# UltiMem_v1_01.net
KiCad netlist of a schematic drawn in EAGLE
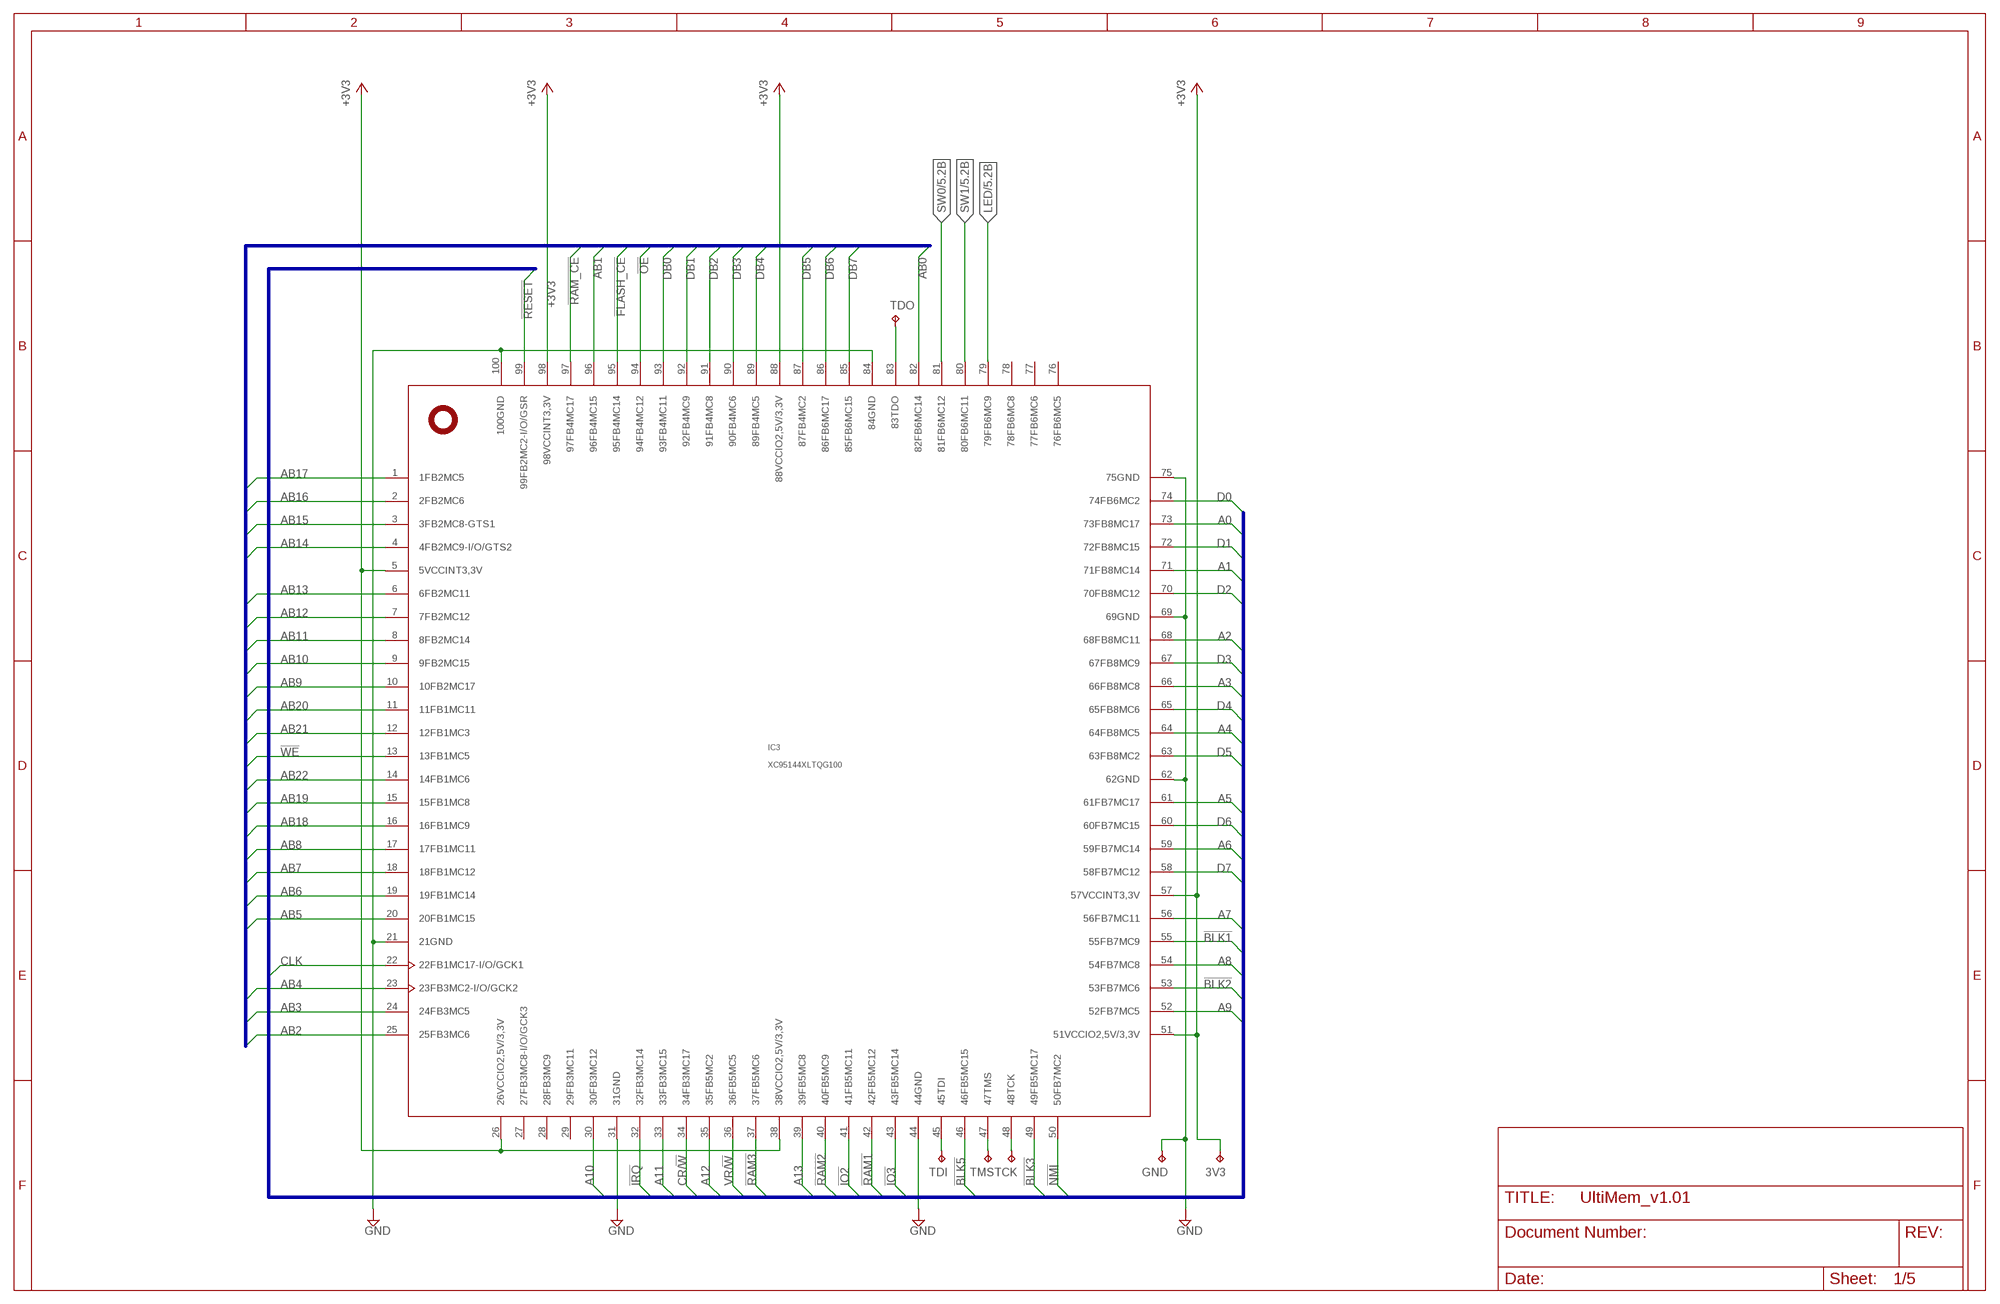
[diagram p0: schematic, sheet 1]
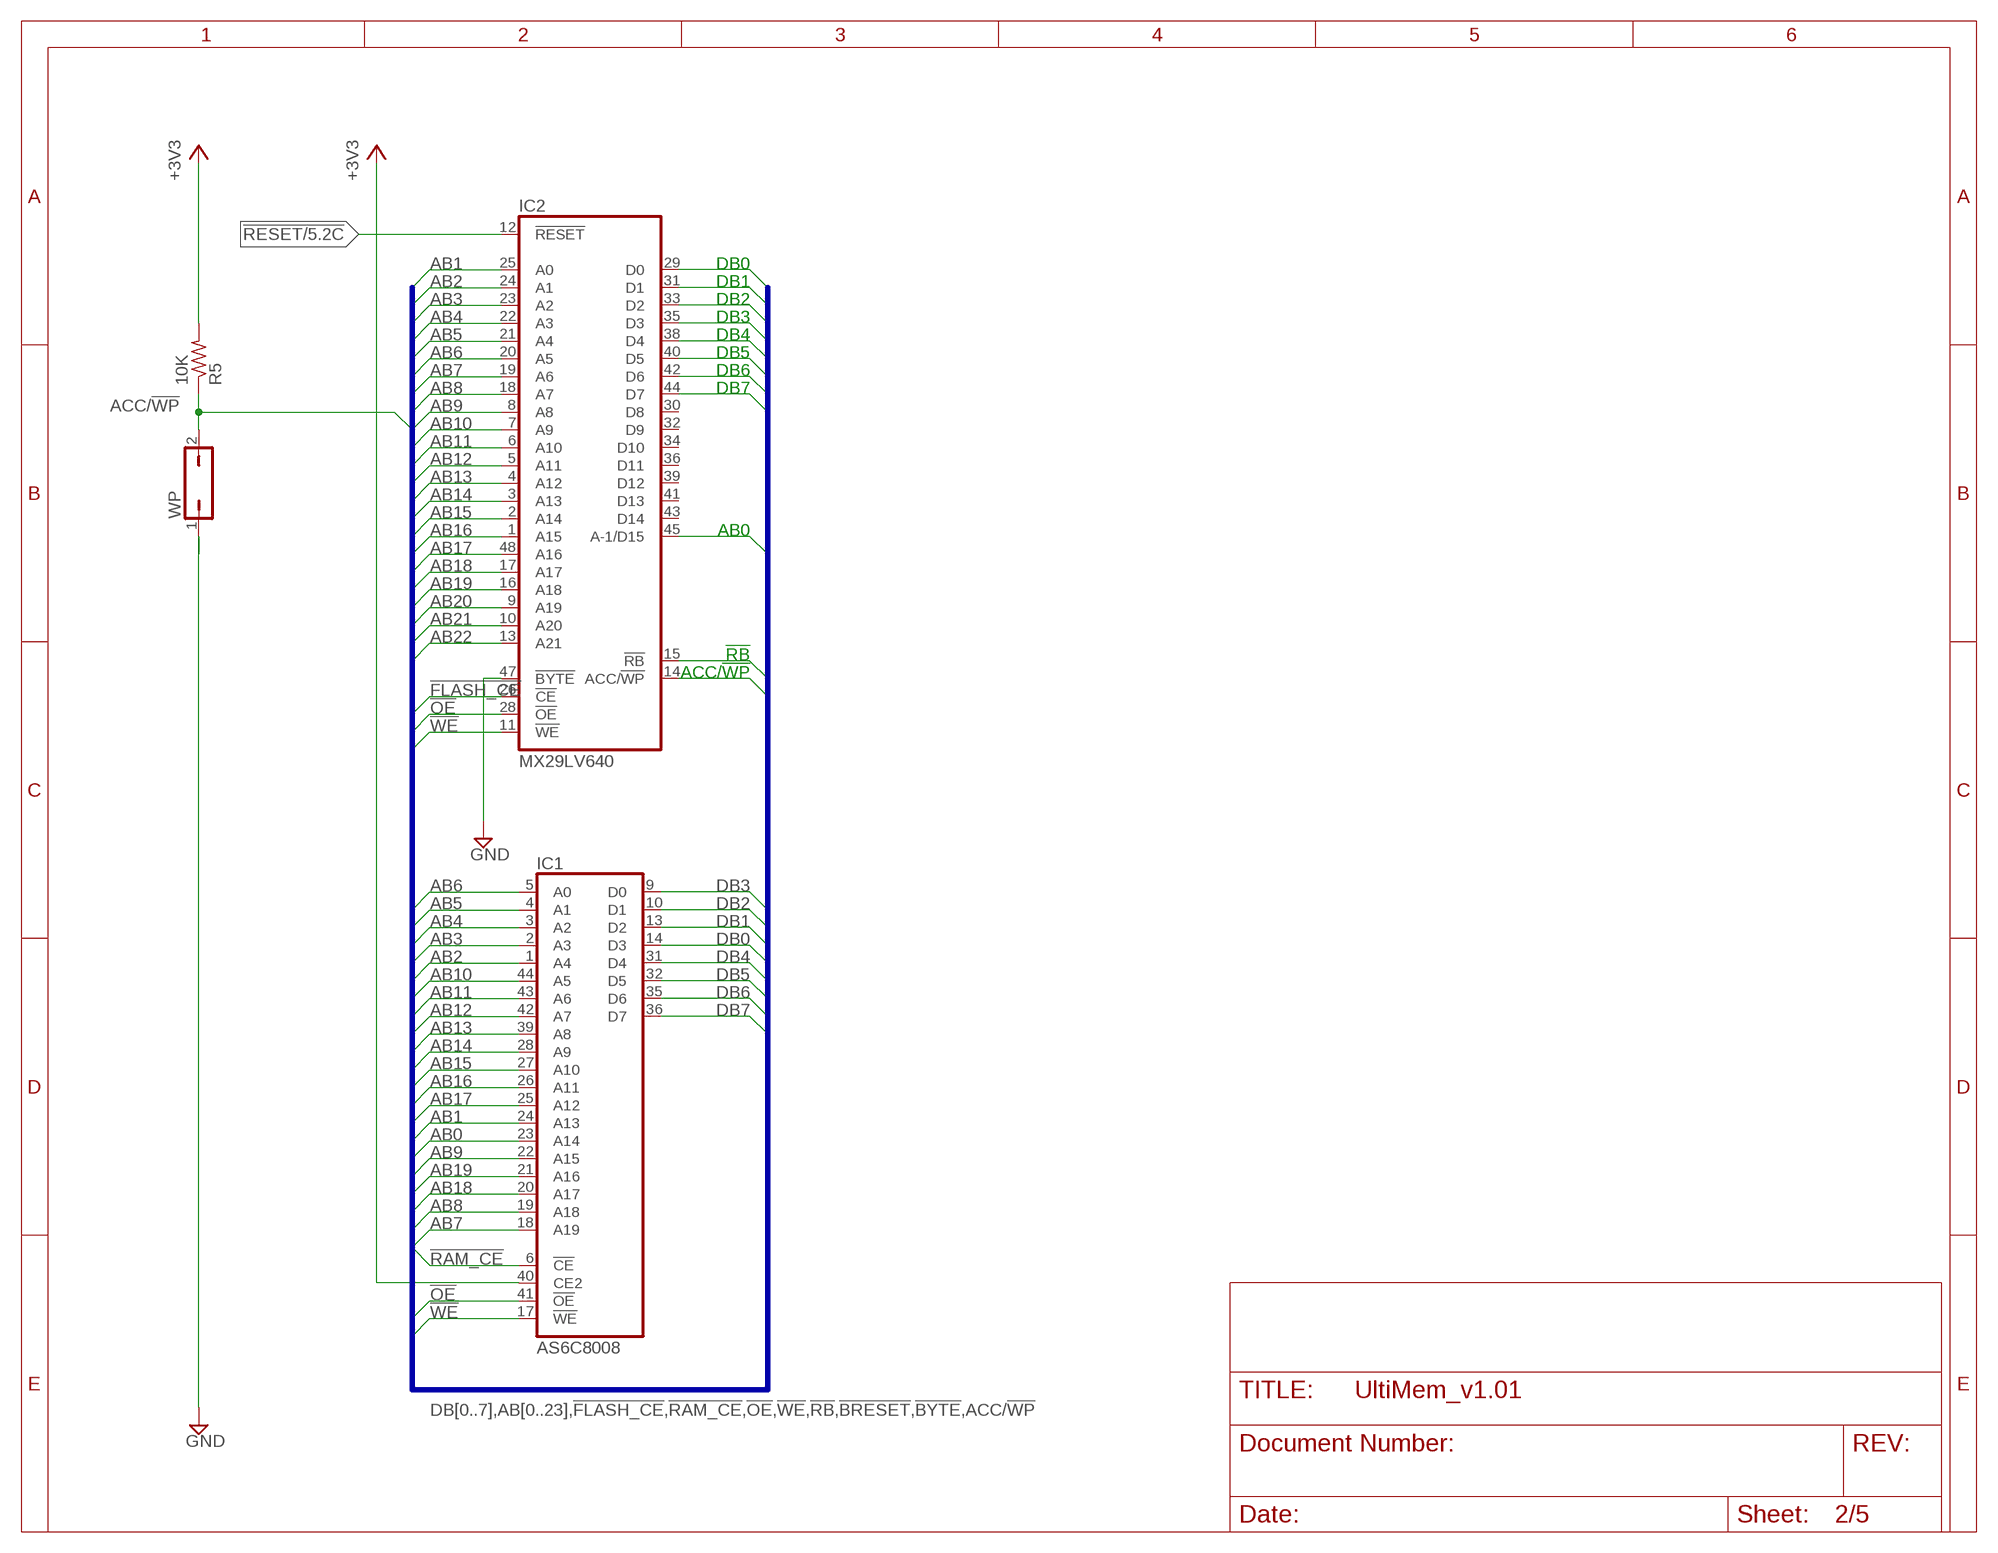
[diagram p1: schematic, sheet 2]
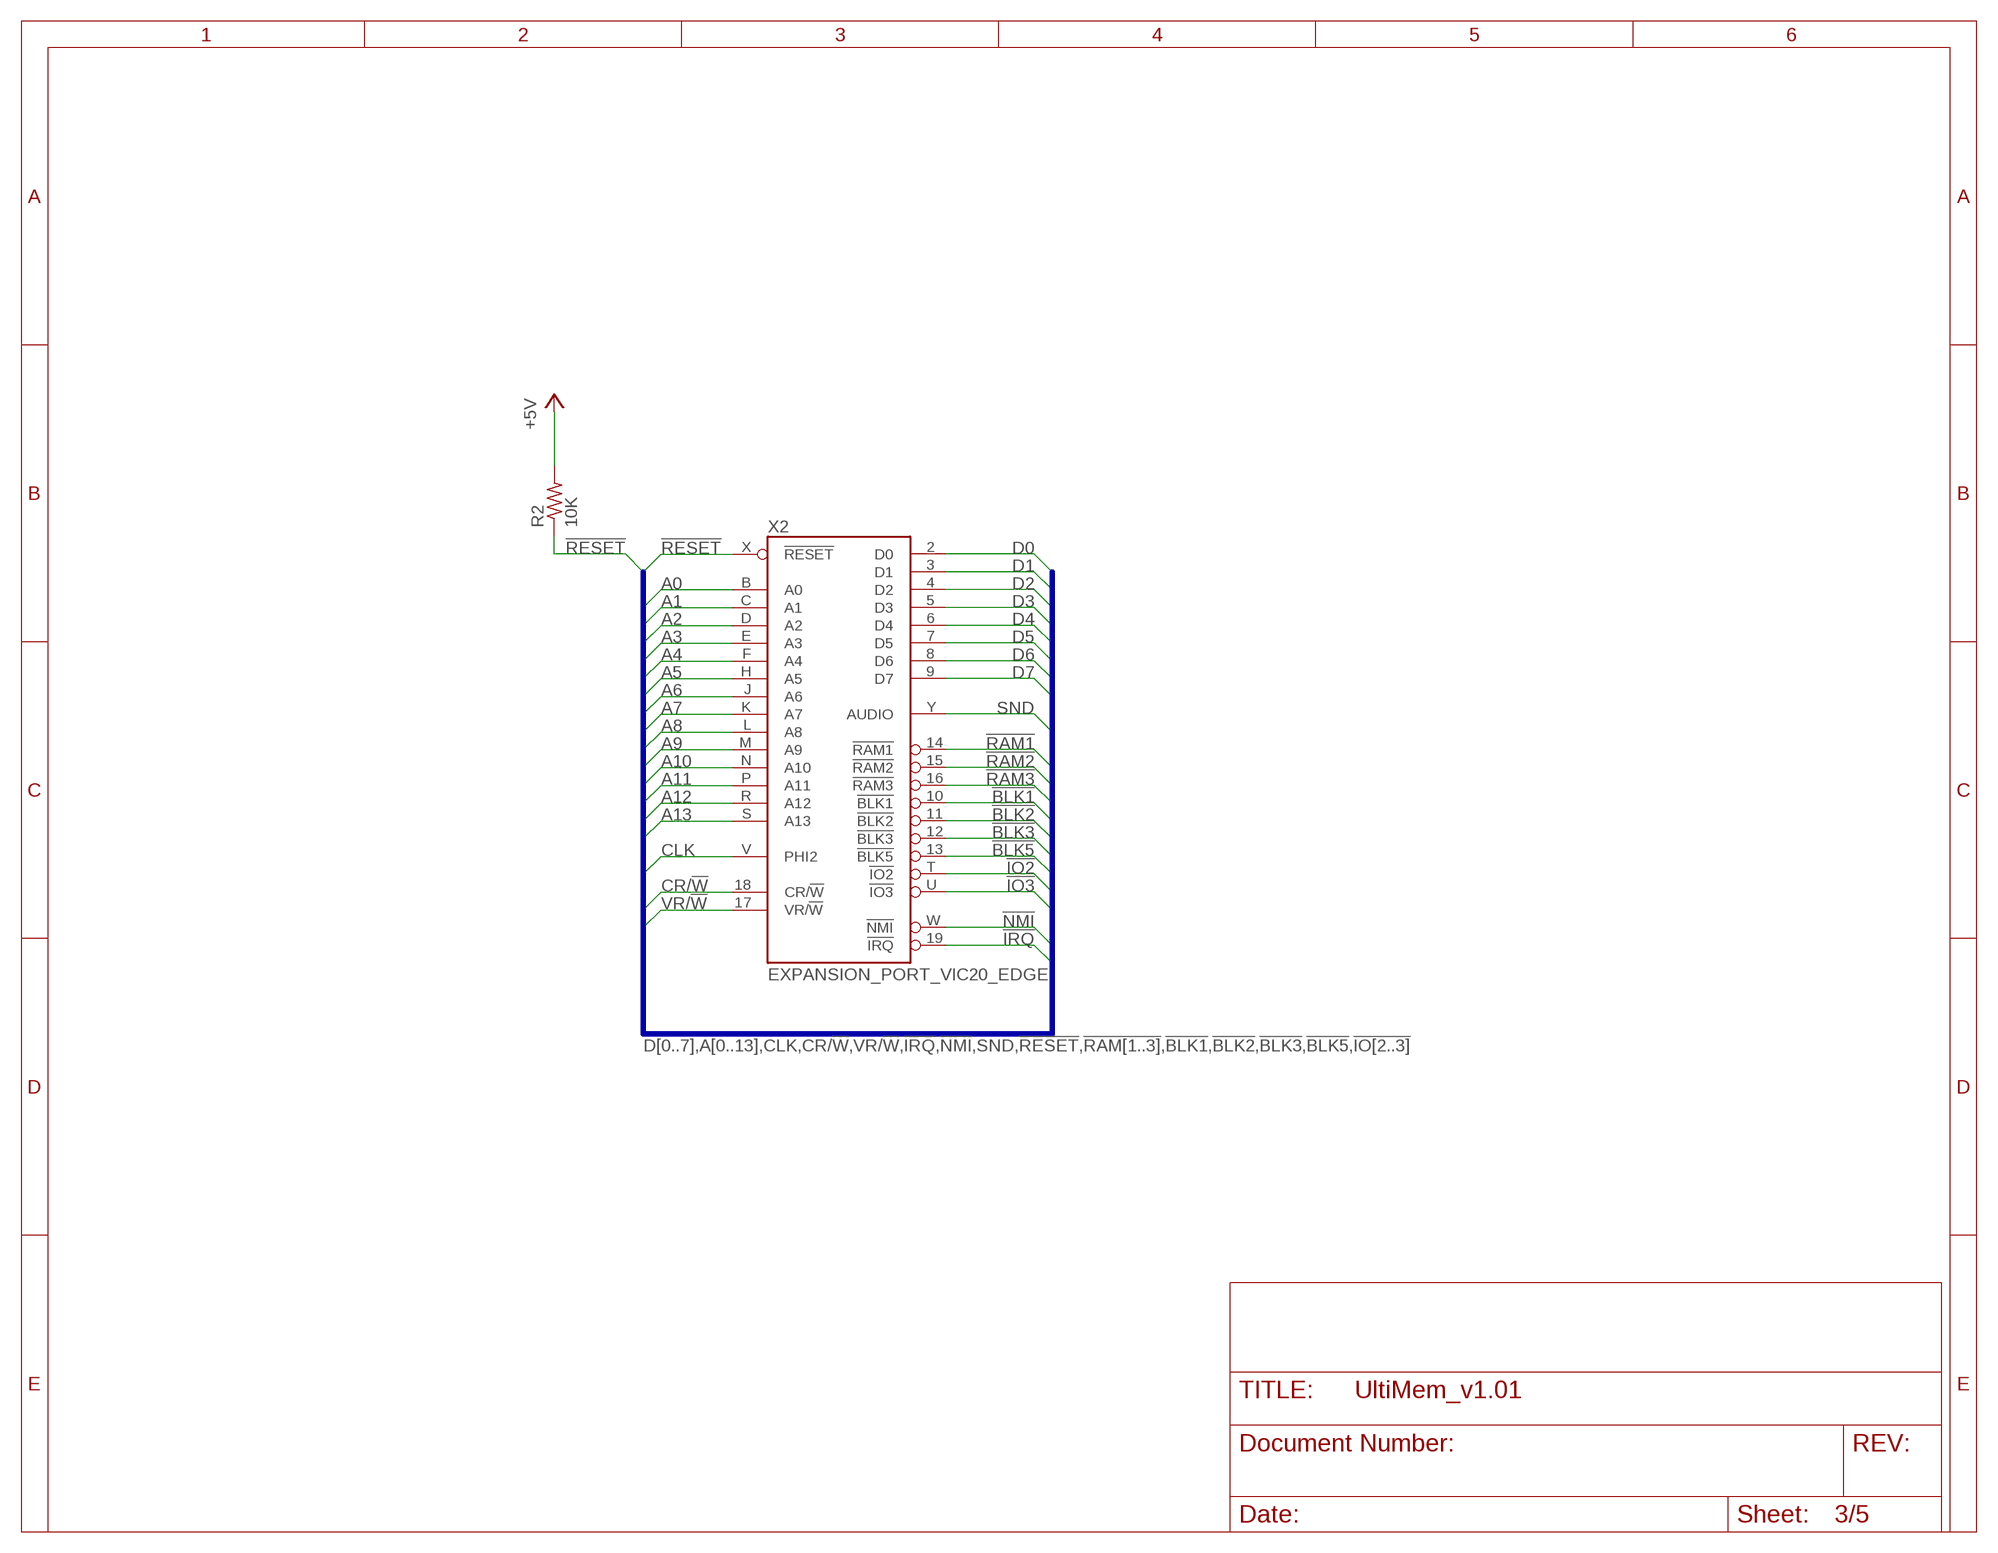
[diagram p2: schematic, sheet 3]
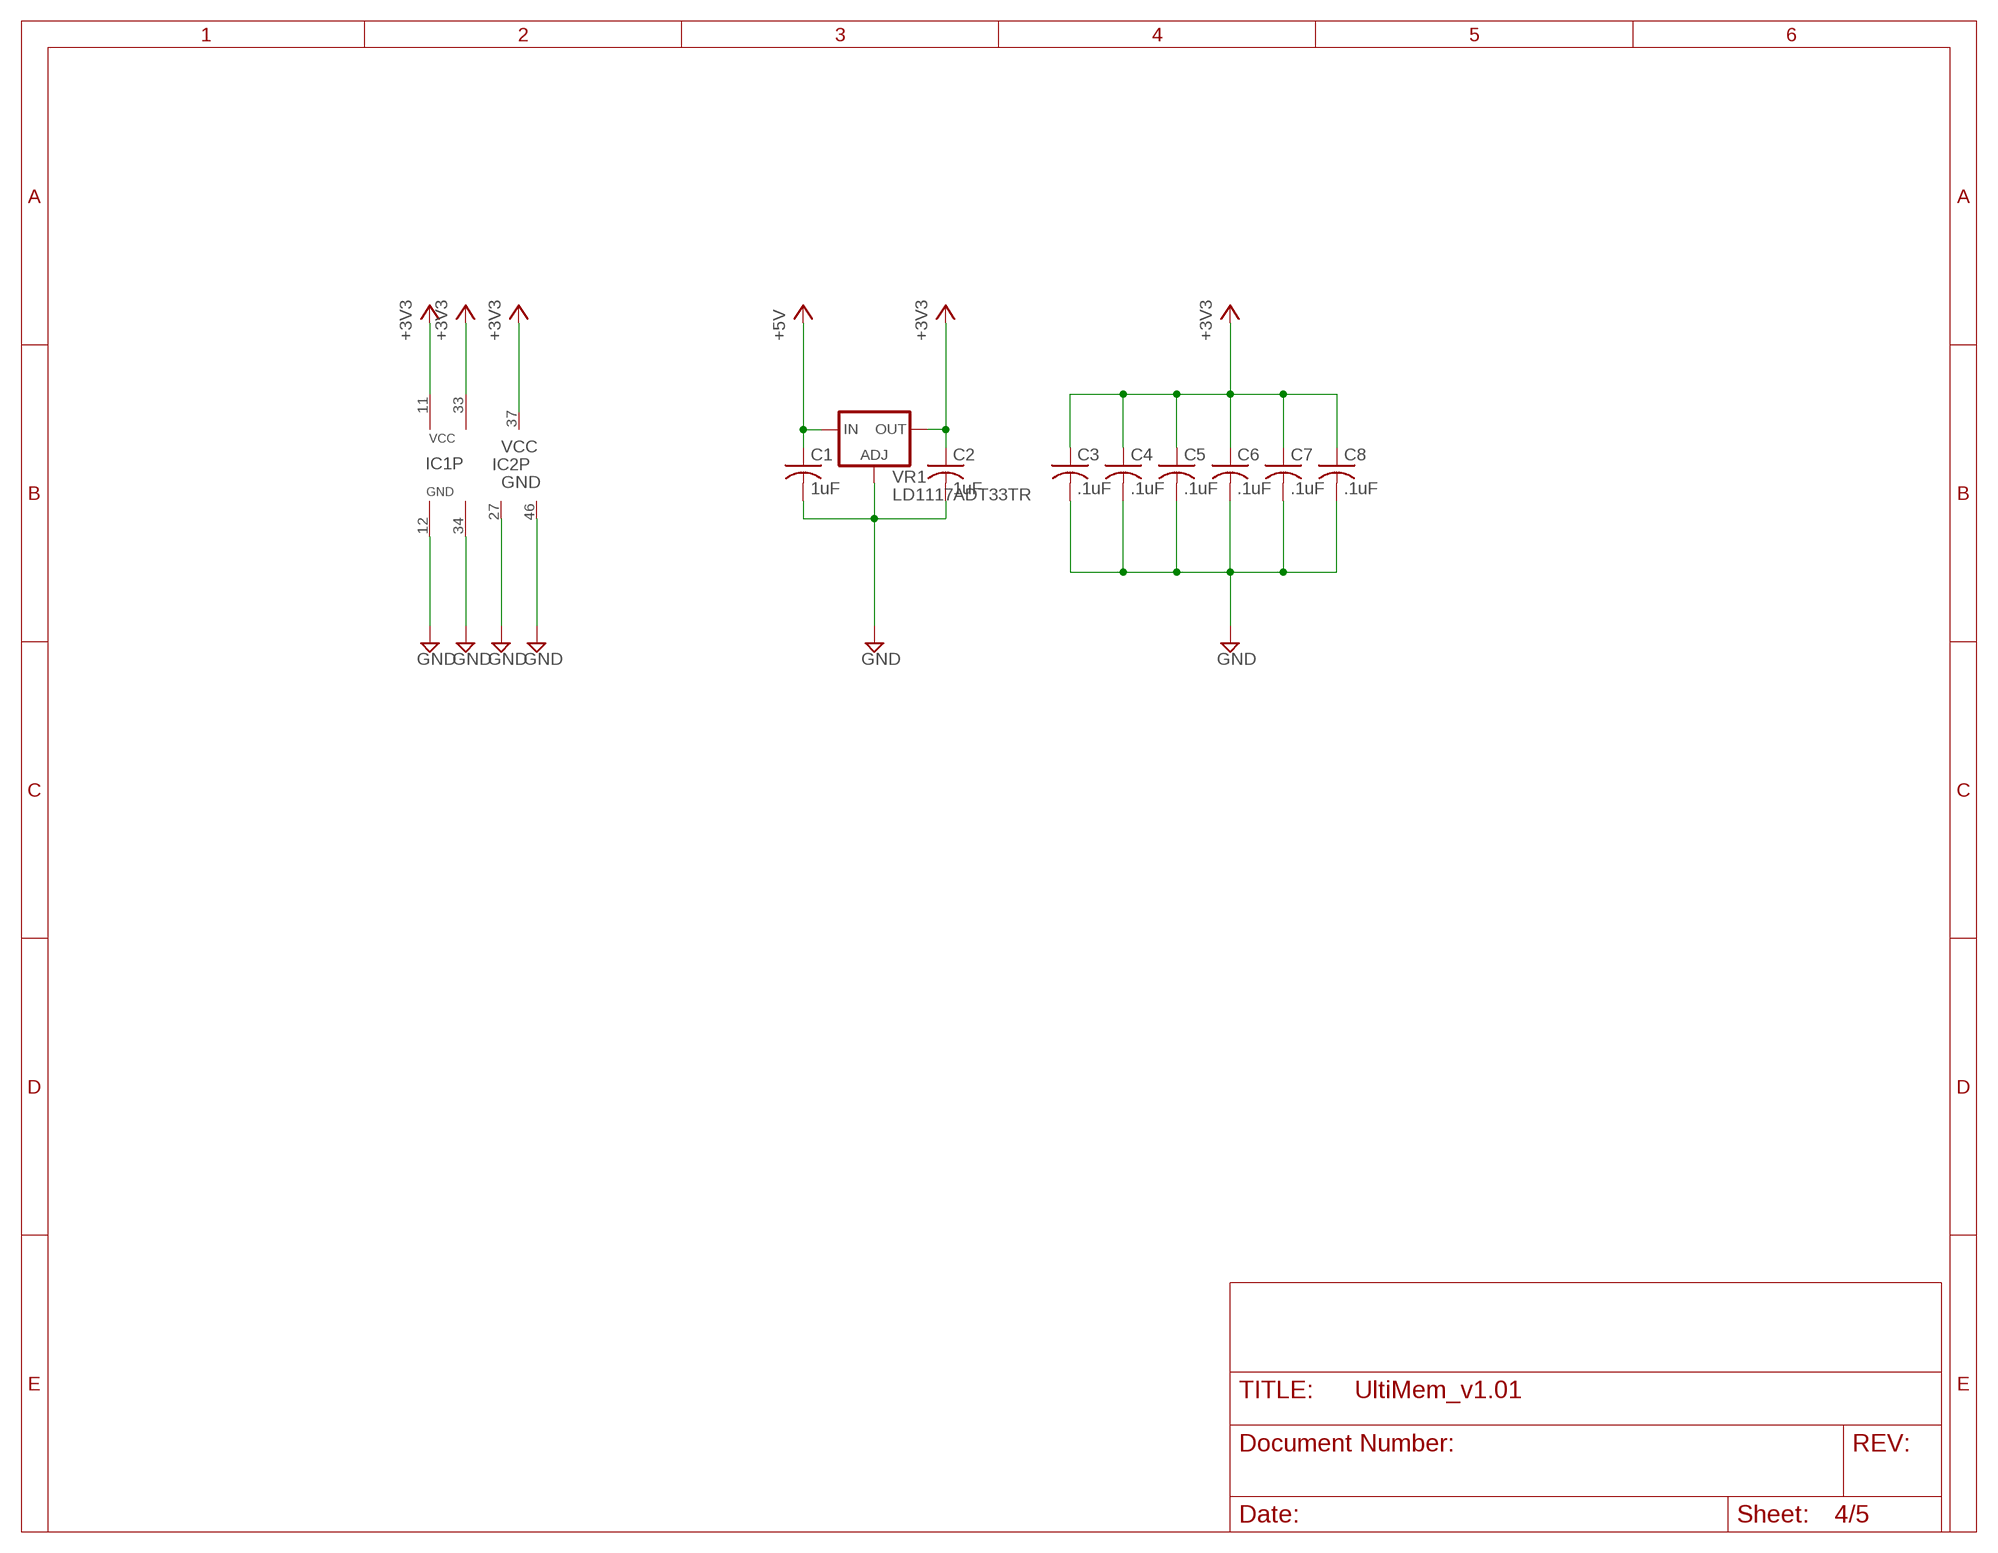
[diagram p3: schematic, sheet 4]
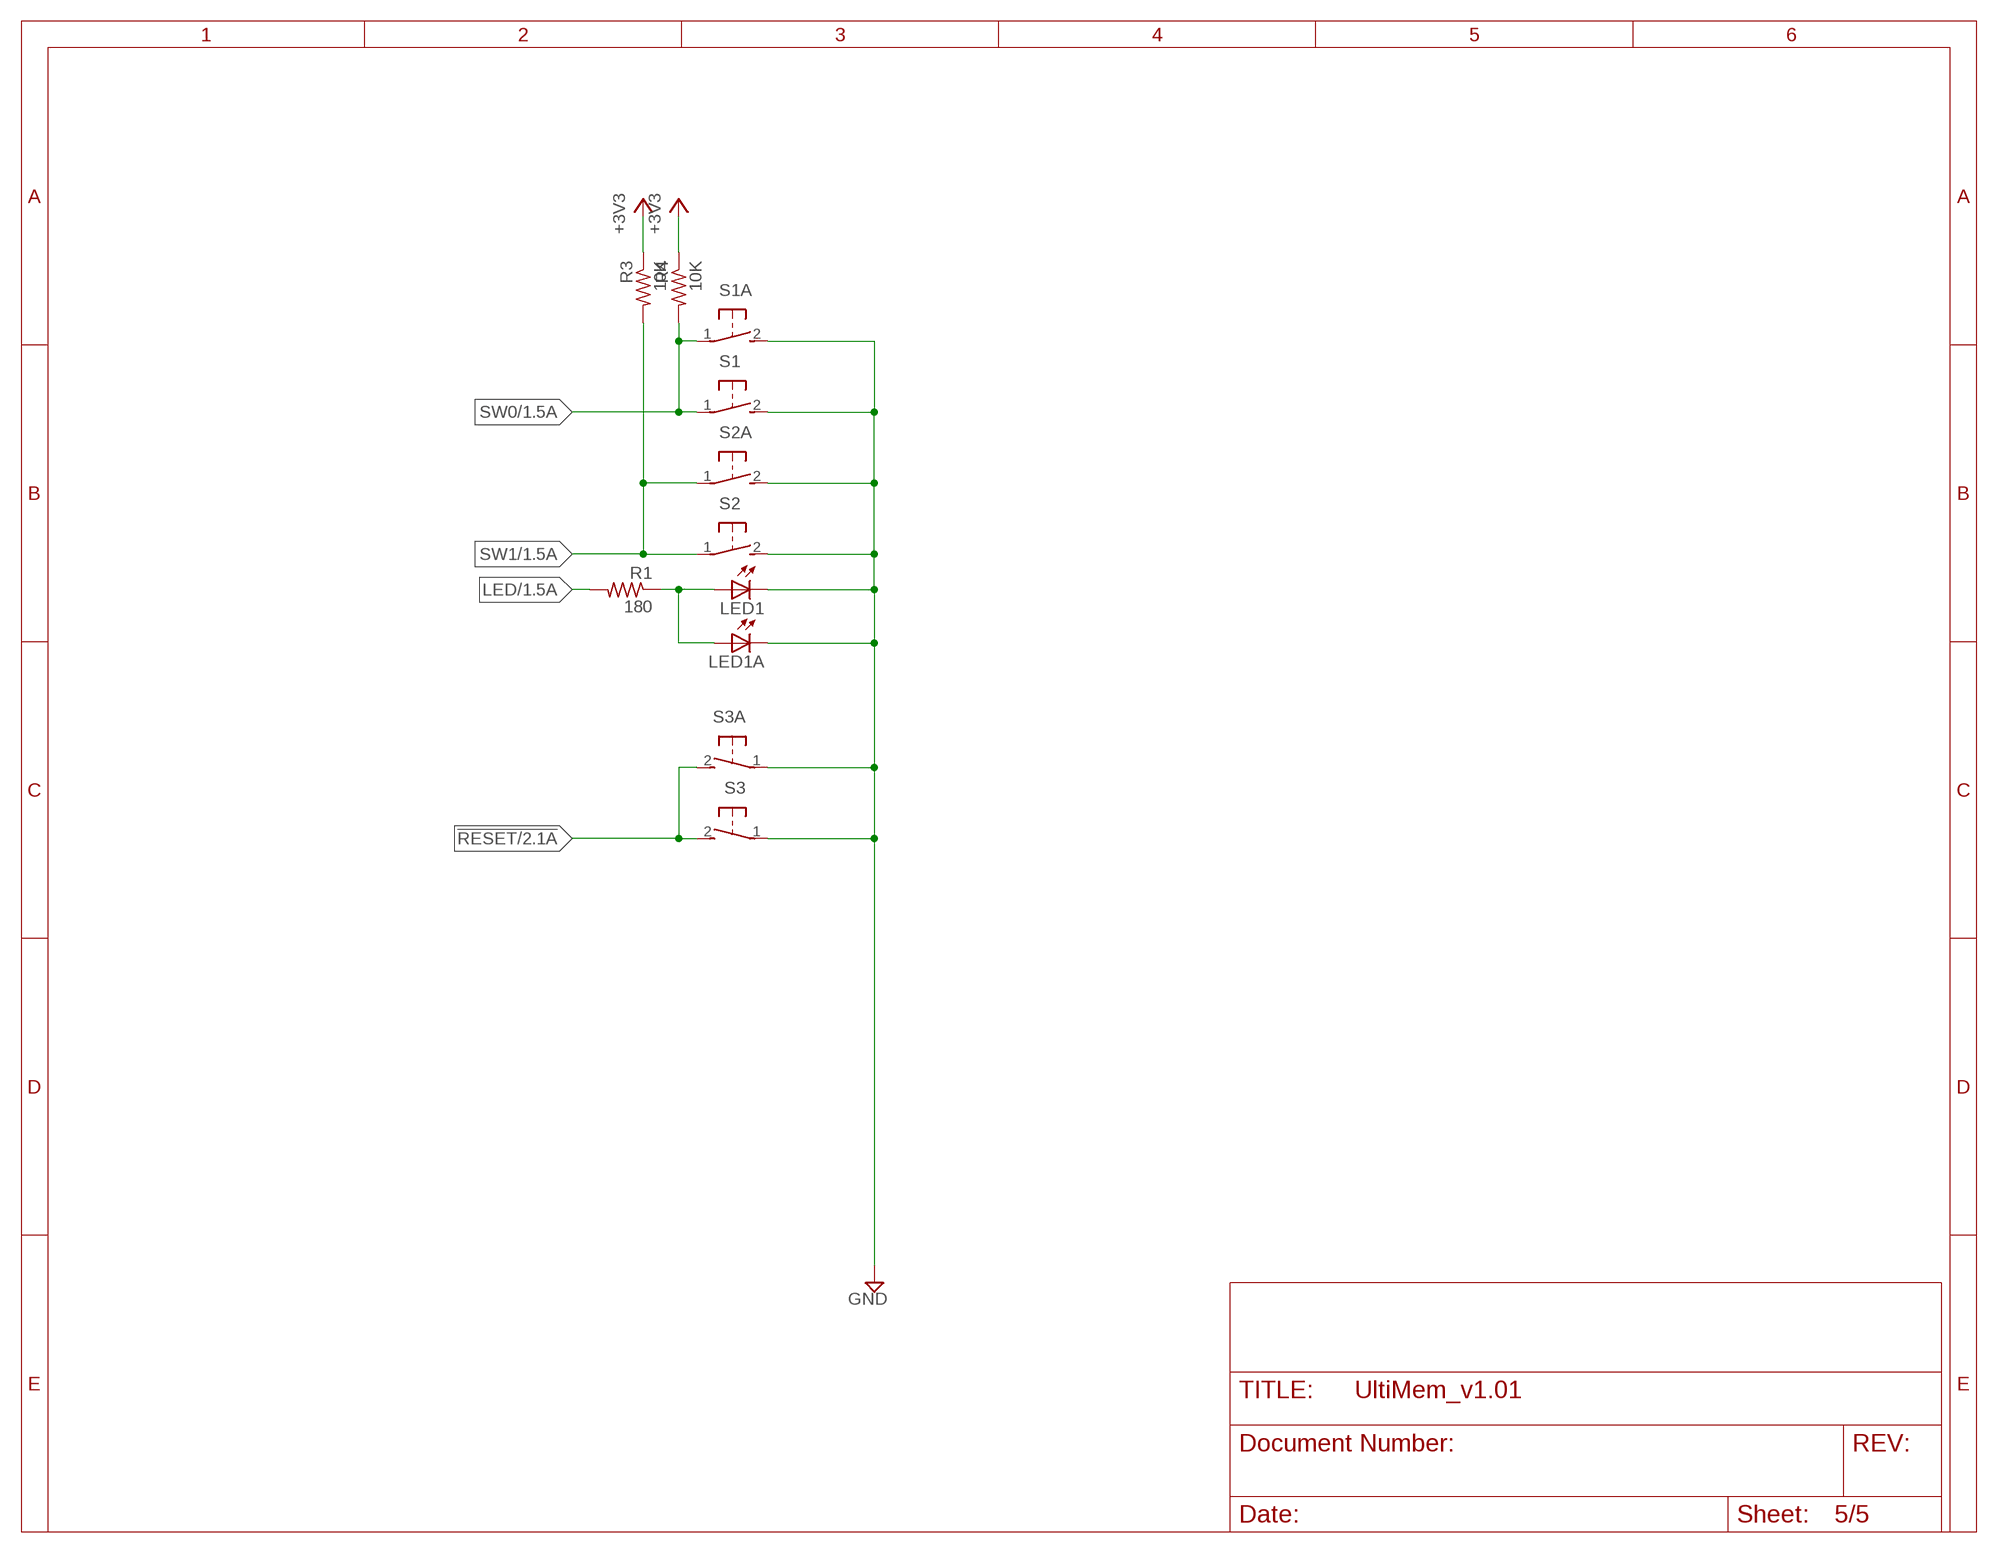
[diagram p4: schematic, sheet 5]

(export (version "E")
  (design (tool "Eeschema 10.0.6"))
  (components
    (comp (ref "C1")
      (value "1uF")
      (footprint "eagle-import:C0402")
      (libsource (lib "eagle-import") (part "C-USC0402"))
    )
    (comp (ref "C2")
      (value "1uF")
      (footprint "eagle-import:C0402")
      (libsource (lib "eagle-import") (part "C-USC0402"))
    )
    (comp (ref "C3")
      (value ".1uF")
      (footprint "eagle-import:C0402")
      (libsource (lib "eagle-import") (part "C-USC0402"))
    )
    (comp (ref "C4")
      (value ".1uF")
      (footprint "eagle-import:C0402")
      (libsource (lib "eagle-import") (part "C-USC0402"))
    )
    (comp (ref "C5")
      (value ".1uF")
      (footprint "eagle-import:C0402")
      (libsource (lib "eagle-import") (part "C-USC0402"))
    )
    (comp (ref "C6")
      (value ".1uF")
      (footprint "eagle-import:C0402")
      (libsource (lib "eagle-import") (part "C-USC0402"))
    )
    (comp (ref "C7")
      (value ".1uF")
      (footprint "eagle-import:C0402")
      (libsource (lib "eagle-import") (part "C-USC0402"))
    )
    (comp (ref "C8")
      (value ".1uF")
      (footprint "eagle-import:C0402")
      (libsource (lib "eagle-import") (part "C-USC0402"))
    )
    (comp (ref "IC1")
      (value "AS6C8008")
      (footprint "eagle-import:TSOP44")
      (libsource (lib "eagle-import") (part "AS6C8008"))
    )
    (comp (ref "IC2")
      (value "MX29LV640")
      (footprint "eagle-import:TSOP48")
      (libsource (lib "eagle-import") (part "MX29LV640"))
    )
    (comp (ref "VR1")
      (value "LD1117ADT33TR")
      (footprint "eagle-import:DPACK")
      (libsource (lib "eagle-import") (part "LD117A?DT33TR"))
    )
    (comp (ref "R5")
      (value "10K")
      (footprint "eagle-import:R0402")
      (libsource (lib "eagle-import") (part "R-US_R0402"))
    )
    (comp (ref "WP")
      (value "JP1Q")
      (footprint "eagle-import:JP1")
      (libsource (lib "eagle-import") (part "JP1Q"))
    )
    (comp (ref "R2")
      (value "10K")
      (footprint "eagle-import:R0402")
      (libsource (lib "eagle-import") (part "resistor_R-US_R0402"))
    )
    (comp (ref "X2")
      (value "EXPANSION_PORT_VIC20_EDGE")
      (footprint "eagle-import:MA156-22-2")
      (libsource (lib "eagle-import") (part "EXPANSION_PORT_VIC20_EDGE"))
    )
    (comp (ref "LED1")
      (value "LED3MM")
      (footprint "eagle-import:LED3MM")
      (libsource (lib "eagle-import") (part "LED3MM"))
    )
    (comp (ref "LED1A")
      (value "LED3MM")
      (footprint "eagle-import:LED3MM")
      (libsource (lib "eagle-import") (part "LED3MM"))
    )
    (comp (ref "R1")
      (value "180")
      (footprint "eagle-import:R0402")
      (libsource (lib "eagle-import") (part "R-US_R0402"))
    )
    (comp (ref "R3")
      (value "10K")
      (footprint "eagle-import:R0402")
      (libsource (lib "eagle-import") (part "R-US_R0402"))
    )
    (comp (ref "R4")
      (value "10K")
      (footprint "eagle-import:R0402")
      (libsource (lib "eagle-import") (part "R-US_R0402"))
    )
    (comp (ref "S1")
      (value "31-XX")
      (footprint "eagle-import:B3F-31XX")
      (fields (field (name "MPN") "B3F-3100"))
      (libsource (lib "eagle-import") (part "31-XX"))
    )
    (comp (ref "S1A")
      (value "31-XX")
      (footprint "eagle-import:B3F-31XX")
      (fields (field (name "MPN") "B3F-3100"))
      (libsource (lib "eagle-import") (part "31-XX"))
    )
    (comp (ref "S2")
      (value "31-XX")
      (footprint "eagle-import:B3F-31XX")
      (fields (field (name "MPN") "B3F-3100"))
      (libsource (lib "eagle-import") (part "31-XX"))
    )
    (comp (ref "S2A")
      (value "31-XX")
      (footprint "eagle-import:B3F-31XX")
      (fields (field (name "MPN") "B3F-3100"))
      (libsource (lib "eagle-import") (part "31-XX"))
    )
    (comp (ref "S3")
      (value "31-XX")
      (footprint "eagle-import:B3F-31XX")
      (fields (field (name "MPN") "B3F-3100"))
      (libsource (lib "eagle-import") (part "31-XX"))
    )
    (comp (ref "S3A")
      (value "31-XX")
      (footprint "eagle-import:B3F-31XX")
      (fields (field (name "MPN") "B3F-3100"))
      (libsource (lib "eagle-import") (part "31-XX"))
    )
    (comp (ref "3V3")
      (value "TPTP08R")
      (footprint "eagle-import:TP08R")
      (libsource (lib "eagle-import") (part "TPTP08R"))
    )
    (comp (ref "GND")
      (value "TPTP08R")
      (footprint "eagle-import:TP08R")
      (libsource (lib "eagle-import") (part "TPTP08R"))
    )
    (comp (ref "IC3")
      (value "XC95144XLTQG100")
      (footprint "eagle-import:TQFP100")
      (libsource (lib "eagle-import") (part "XC95144XLTQG100"))
    )
    (comp (ref "TCK")
      (value "TPTP08R")
      (footprint "eagle-import:TP08R")
      (libsource (lib "eagle-import") (part "TPTP08R"))
    )
    (comp (ref "TDI")
      (value "TPTP08R")
      (footprint "eagle-import:TP08R")
      (libsource (lib "eagle-import") (part "TPTP08R"))
    )
    (comp (ref "TDO")
      (value "TPTP08R")
      (footprint "eagle-import:TP08R")
      (libsource (lib "eagle-import") (part "TPTP08R"))
    )
    (comp (ref "TMS")
      (value "TPTP08R")
      (footprint "eagle-import:TP08R")
      (libsource (lib "eagle-import") (part "TPTP08R"))
    )
  )
  (nets
    (net (code "3") (name "+3V3") (class "Default")
      (node (ref "3V3") (pin "TP") (pinfunction "TP_TP") (pintype "input"))
      (node (ref "C2") (pin "1") (pinfunction "1_1") (pintype "passive"))
      (node (ref "C3") (pin "1") (pinfunction "1_1") (pintype "passive"))
      (node (ref "C4") (pin "1") (pinfunction "1_1") (pintype "passive"))
      (node (ref "C5") (pin "1") (pinfunction "1_1") (pintype "passive"))
      (node (ref "C6") (pin "1") (pinfunction "1_1") (pintype "passive"))
      (node (ref "C7") (pin "1") (pinfunction "1_1") (pintype "passive"))
      (node (ref "C8") (pin "1") (pinfunction "1_1") (pintype "passive"))
      (node (ref "IC1") (pin "11") (pinfunction "VCC_11") (pintype "power_in"))
      (node (ref "IC1") (pin "33") (pinfunction "VCC_33") (pintype "power_in"))
      (node (ref "IC1") (pin "40") (pinfunction "CE2_40") (pintype "input"))
      (node (ref "IC2") (pin "37") (pinfunction "VCC_37") (pintype "power_in"))
      (node (ref "IC3") (pin "26") (pinfunction "26VCCIO2,5V/3,3V_26") (pintype "power_in"))
      (node (ref "IC3") (pin "38") (pinfunction "38VCCIO2,5V/3,3V_38") (pintype "power_in"))
      (node (ref "IC3") (pin "5") (pinfunction "5VCCINT3,3V_5") (pintype "power_in"))
      (node (ref "IC3") (pin "51") (pinfunction "51VCCIO2,5V/3,3V_51") (pintype "power_in"))
      (node (ref "IC3") (pin "57") (pinfunction "57VCCINT3,3V_57") (pintype "power_in"))
      (node (ref "IC3") (pin "88") (pinfunction "88VCCIO2,5V/3,3V_88") (pintype "power_in"))
      (node (ref "IC3") (pin "98") (pinfunction "98VCCINT3,3V_98") (pintype "bidirectional"))
      (node (ref "R3") (pin "1") (pinfunction "1_1") (pintype "passive"))
      (node (ref "R4") (pin "1") (pinfunction "1_1") (pintype "passive"))
      (node (ref "R5") (pin "2") (pinfunction "2_2") (pintype "passive"))
      (node (ref "VR1") (pin "4") (pinfunction "OUT_4") (pintype "passive"))
    )
    (net (code "4") (name "+5V") (class "Default")
      (node (ref "C1") (pin "1") (pinfunction "1_1") (pintype "passive"))
      (node (ref "R2") (pin "2") (pinfunction "2_2") (pintype "passive"))
      (node (ref "VR1") (pin "3") (pinfunction "IN_3") (pintype "input"))
    )
    (net (code "7") (name "A0") (class "Default")
      (node (ref "IC3") (pin "73") (pinfunction "73FB8MC17_73") (pintype "bidirectional"))
      (node (ref "X2") (pin "B") (pinfunction "A0_B") (pintype "output"))
    )
    (net (code "8") (name "A1") (class "Default")
      (node (ref "IC3") (pin "71") (pinfunction "71FB8MC14_71") (pintype "bidirectional"))
      (node (ref "X2") (pin "C") (pinfunction "A1_C") (pintype "output"))
    )
    (net (code "9") (name "A2") (class "Default")
      (node (ref "IC3") (pin "68") (pinfunction "68FB8MC11_68") (pintype "bidirectional"))
      (node (ref "X2") (pin "D") (pinfunction "A2_D") (pintype "output"))
    )
    (net (code "10") (name "A3") (class "Default")
      (node (ref "IC3") (pin "66") (pinfunction "66FB8MC8_66") (pintype "bidirectional"))
      (node (ref "X2") (pin "E") (pinfunction "A3_E") (pintype "output"))
    )
    (net (code "11") (name "A4") (class "Default")
      (node (ref "IC3") (pin "64") (pinfunction "64FB8MC5_64") (pintype "bidirectional"))
      (node (ref "X2") (pin "F") (pinfunction "A4_F") (pintype "output"))
    )
    (net (code "12") (name "A5") (class "Default")
      (node (ref "IC3") (pin "61") (pinfunction "61FB7MC17_61") (pintype "bidirectional"))
      (node (ref "X2") (pin "H") (pinfunction "A5_H") (pintype "output"))
    )
    (net (code "13") (name "A6") (class "Default")
      (node (ref "IC3") (pin "59") (pinfunction "59FB7MC14_59") (pintype "bidirectional"))
      (node (ref "X2") (pin "J") (pinfunction "A6_J") (pintype "output"))
    )
    (net (code "14") (name "A7") (class "Default")
      (node (ref "IC3") (pin "56") (pinfunction "56FB7MC11_56") (pintype "bidirectional"))
      (node (ref "X2") (pin "K") (pinfunction "A7_K") (pintype "output"))
    )
    (net (code "15") (name "A8") (class "Default")
      (node (ref "IC3") (pin "54") (pinfunction "54FB7MC8_54") (pintype "bidirectional"))
      (node (ref "X2") (pin "L") (pinfunction "A8_L") (pintype "output"))
    )
    (net (code "16") (name "A9") (class "Default")
      (node (ref "IC3") (pin "52") (pinfunction "52FB7MC5_52") (pintype "bidirectional"))
      (node (ref "X2") (pin "M") (pinfunction "A9_M") (pintype "output"))
    )
    (net (code "17") (name "A10") (class "Default")
      (node (ref "IC3") (pin "30") (pinfunction "30FB3MC12_30") (pintype "bidirectional"))
      (node (ref "X2") (pin "N") (pinfunction "A10_N") (pintype "output"))
    )
    (net (code "18") (name "A11") (class "Default")
      (node (ref "IC3") (pin "33") (pinfunction "33FB3MC15_33") (pintype "bidirectional"))
      (node (ref "X2") (pin "P") (pinfunction "A11_P") (pintype "output"))
    )
    (net (code "19") (name "A12") (class "Default")
      (node (ref "IC3") (pin "35") (pinfunction "35FB5MC2_35") (pintype "bidirectional"))
      (node (ref "X2") (pin "R") (pinfunction "A12_R") (pintype "output"))
    )
    (net (code "20") (name "A13") (class "Default")
      (node (ref "IC3") (pin "39") (pinfunction "39FB5MC8_39") (pintype "bidirectional"))
      (node (ref "X2") (pin "S") (pinfunction "A13_S") (pintype "output"))
    )
    (net (code "21") (name "AB0") (class "Default")
      (node (ref "IC1") (pin "23") (pinfunction "A14_23") (pintype "input"))
      (node (ref "IC2") (pin "45") (pinfunction "A-1/D15_45") (pintype "tri_state"))
      (node (ref "IC3") (pin "82") (pinfunction "82FB6MC14_82") (pintype "bidirectional"))
    )
    (net (code "22") (name "AB1") (class "Default")
      (node (ref "IC1") (pin "24") (pinfunction "A13_24") (pintype "input"))
      (node (ref "IC2") (pin "25") (pinfunction "A0_25") (pintype "input"))
      (node (ref "IC3") (pin "96") (pinfunction "96FB4MC15_96") (pintype "bidirectional"))
    )
    (net (code "23") (name "AB2") (class "Default")
      (node (ref "IC1") (pin "1") (pinfunction "A4_1") (pintype "input"))
      (node (ref "IC2") (pin "24") (pinfunction "A1_24") (pintype "input"))
      (node (ref "IC3") (pin "25") (pinfunction "25FB3MC6_25") (pintype "bidirectional"))
    )
    (net (code "24") (name "AB3") (class "Default")
      (node (ref "IC1") (pin "2") (pinfunction "A3_2") (pintype "input"))
      (node (ref "IC2") (pin "23") (pinfunction "A2_23") (pintype "input"))
      (node (ref "IC3") (pin "24") (pinfunction "24FB3MC5_24") (pintype "bidirectional"))
    )
    (net (code "25") (name "AB4") (class "Default")
      (node (ref "IC1") (pin "3") (pinfunction "A2_3") (pintype "input"))
      (node (ref "IC2") (pin "22") (pinfunction "A3_22") (pintype "input"))
      (node (ref "IC3") (pin "23") (pinfunction "23FB3MC2-I/O/GCK2_23") (pintype "bidirectional"))
    )
    (net (code "26") (name "AB5") (class "Default")
      (node (ref "IC1") (pin "4") (pinfunction "A1_4") (pintype "input"))
      (node (ref "IC2") (pin "21") (pinfunction "A4_21") (pintype "input"))
      (node (ref "IC3") (pin "20") (pinfunction "20FB1MC15_20") (pintype "bidirectional"))
    )
    (net (code "27") (name "AB6") (class "Default")
      (node (ref "IC1") (pin "5") (pinfunction "A0_5") (pintype "input"))
      (node (ref "IC2") (pin "20") (pinfunction "A5_20") (pintype "input"))
      (node (ref "IC3") (pin "19") (pinfunction "19FB1MC14_19") (pintype "bidirectional"))
    )
    (net (code "28") (name "AB7") (class "Default")
      (node (ref "IC1") (pin "18") (pinfunction "A19_18") (pintype "input"))
      (node (ref "IC2") (pin "19") (pinfunction "A6_19") (pintype "input"))
      (node (ref "IC3") (pin "18") (pinfunction "18FB1MC12_18") (pintype "bidirectional"))
    )
    (net (code "29") (name "AB8") (class "Default")
      (node (ref "IC1") (pin "19") (pinfunction "A18_19") (pintype "input"))
      (node (ref "IC2") (pin "18") (pinfunction "A7_18") (pintype "input"))
      (node (ref "IC3") (pin "17") (pinfunction "17FB1MC11_17") (pintype "bidirectional"))
    )
    (net (code "30") (name "AB9") (class "Default")
      (node (ref "IC1") (pin "22") (pinfunction "A15_22") (pintype "input"))
      (node (ref "IC2") (pin "8") (pinfunction "A8_8") (pintype "input"))
      (node (ref "IC3") (pin "10") (pinfunction "10FB2MC17_10") (pintype "bidirectional"))
    )
    (net (code "31") (name "AB10") (class "Default")
      (node (ref "IC1") (pin "44") (pinfunction "A5_44") (pintype "input"))
      (node (ref "IC2") (pin "7") (pinfunction "A9_7") (pintype "input"))
      (node (ref "IC3") (pin "9") (pinfunction "9FB2MC15_9") (pintype "bidirectional"))
    )
    (net (code "32") (name "AB11") (class "Default")
      (node (ref "IC1") (pin "43") (pinfunction "A6_43") (pintype "input"))
      (node (ref "IC2") (pin "6") (pinfunction "A10_6") (pintype "input"))
      (node (ref "IC3") (pin "8") (pinfunction "8FB2MC14_8") (pintype "bidirectional"))
    )
    (net (code "33") (name "AB12") (class "Default")
      (node (ref "IC1") (pin "42") (pinfunction "A7_42") (pintype "input"))
      (node (ref "IC2") (pin "5") (pinfunction "A11_5") (pintype "input"))
      (node (ref "IC3") (pin "7") (pinfunction "7FB2MC12_7") (pintype "bidirectional"))
    )
    (net (code "34") (name "AB13") (class "Default")
      (node (ref "IC1") (pin "39") (pinfunction "A8_39") (pintype "input"))
      (node (ref "IC2") (pin "4") (pinfunction "A12_4") (pintype "input"))
      (node (ref "IC3") (pin "6") (pinfunction "6FB2MC11_6") (pintype "bidirectional"))
    )
    (net (code "35") (name "AB14") (class "Default")
      (node (ref "IC1") (pin "28") (pinfunction "A9_28") (pintype "input"))
      (node (ref "IC2") (pin "3") (pinfunction "A13_3") (pintype "input"))
      (node (ref "IC3") (pin "4") (pinfunction "4FB2MC9-I/O/GTS2_4") (pintype "bidirectional"))
    )
    (net (code "36") (name "AB15") (class "Default")
      (node (ref "IC1") (pin "27") (pinfunction "A10_27") (pintype "input"))
      (node (ref "IC2") (pin "2") (pinfunction "A14_2") (pintype "input"))
      (node (ref "IC3") (pin "3") (pinfunction "3FB2MC8-GTS1_3") (pintype "bidirectional"))
    )
    (net (code "37") (name "AB16") (class "Default")
      (node (ref "IC1") (pin "26") (pinfunction "A11_26") (pintype "input"))
      (node (ref "IC2") (pin "1") (pinfunction "A15_1") (pintype "input"))
      (node (ref "IC3") (pin "2") (pinfunction "2FB2MC6_2") (pintype "bidirectional"))
    )
    (net (code "38") (name "AB17") (class "Default")
      (node (ref "IC1") (pin "25") (pinfunction "A12_25") (pintype "input"))
      (node (ref "IC2") (pin "48") (pinfunction "A16_48") (pintype "input"))
      (node (ref "IC3") (pin "1") (pinfunction "1FB2MC5_1") (pintype "bidirectional"))
    )
    (net (code "39") (name "AB18") (class "Default")
      (node (ref "IC1") (pin "20") (pinfunction "A17_20") (pintype "input"))
      (node (ref "IC2") (pin "17") (pinfunction "A17_17") (pintype "input"))
      (node (ref "IC3") (pin "16") (pinfunction "16FB1MC9_16") (pintype "bidirectional"))
    )
    (net (code "40") (name "AB19") (class "Default")
      (node (ref "IC1") (pin "21") (pinfunction "A16_21") (pintype "input"))
      (node (ref "IC2") (pin "16") (pinfunction "A18_16") (pintype "input"))
      (node (ref "IC3") (pin "15") (pinfunction "15FB1MC8_15") (pintype "bidirectional"))
    )
    (net (code "41") (name "AB20") (class "Default")
      (node (ref "IC2") (pin "9") (pinfunction "A19_9") (pintype "input"))
      (node (ref "IC3") (pin "11") (pinfunction "11FB1MC11_11") (pintype "bidirectional"))
    )
    (net (code "42") (name "AB21") (class "Default")
      (node (ref "IC2") (pin "10") (pinfunction "A20_10") (pintype "input"))
      (node (ref "IC3") (pin "12") (pinfunction "12FB1MC3_12") (pintype "bidirectional"))
    )
    (net (code "43") (name "AB22") (class "Default")
      (node (ref "IC2") (pin "13") (pinfunction "A21_13") (pintype "input"))
      (node (ref "IC3") (pin "14") (pinfunction "14FB1MC6_14") (pintype "bidirectional"))
    )
    (net (code "44") (name "ACC{slash}~{WP}") (class "Default")
      (node (ref "IC2") (pin "14") (pinfunction "ACC/~{WP}_14") (pintype "output"))
      (node (ref "R5") (pin "1") (pinfunction "1_1") (pintype "passive"))
      (node (ref "WP") (pin "2") (pinfunction "2_2") (pintype "passive"))
    )
    (net (code "45") (name "CLK") (class "Default")
      (node (ref "IC3") (pin "22") (pinfunction "22FB1MC17-I/O/GCK1_22") (pintype "bidirectional"))
      (node (ref "X2") (pin "V") (pinfunction "PHI2_V") (pintype "output"))
    )
    (net (code "46") (name "CR{slash}~{W}") (class "Default")
      (node (ref "IC3") (pin "34") (pinfunction "34FB3MC17_34") (pintype "bidirectional"))
      (node (ref "X2") (pin "18") (pinfunction "CR/~{W}_18") (pintype "output"))
    )
    (net (code "47") (name "D0") (class "Default")
      (node (ref "IC3") (pin "74") (pinfunction "74FB6MC2_74") (pintype "bidirectional"))
      (node (ref "X2") (pin "2") (pinfunction "D0_2") (pintype "bidirectional"))
    )
    (net (code "48") (name "D1") (class "Default")
      (node (ref "IC3") (pin "72") (pinfunction "72FB8MC15_72") (pintype "bidirectional"))
      (node (ref "X2") (pin "3") (pinfunction "D1_3") (pintype "bidirectional"))
    )
    (net (code "49") (name "D2") (class "Default")
      (node (ref "IC3") (pin "70") (pinfunction "70FB8MC12_70") (pintype "bidirectional"))
      (node (ref "X2") (pin "4") (pinfunction "D2_4") (pintype "bidirectional"))
    )
    (net (code "50") (name "D3") (class "Default")
      (node (ref "IC3") (pin "67") (pinfunction "67FB8MC9_67") (pintype "bidirectional"))
      (node (ref "X2") (pin "5") (pinfunction "D3_5") (pintype "bidirectional"))
    )
    (net (code "51") (name "D4") (class "Default")
      (node (ref "IC3") (pin "65") (pinfunction "65FB8MC6_65") (pintype "bidirectional"))
      (node (ref "X2") (pin "6") (pinfunction "D4_6") (pintype "bidirectional"))
    )
    (net (code "52") (name "D5") (class "Default")
      (node (ref "IC3") (pin "63") (pinfunction "63FB8MC2_63") (pintype "bidirectional"))
      (node (ref "X2") (pin "7") (pinfunction "D5_7") (pintype "bidirectional"))
    )
    (net (code "53") (name "D6") (class "Default")
      (node (ref "IC3") (pin "60") (pinfunction "60FB7MC15_60") (pintype "bidirectional"))
      (node (ref "X2") (pin "8") (pinfunction "D6_8") (pintype "bidirectional"))
    )
    (net (code "54") (name "D7") (class "Default")
      (node (ref "IC3") (pin "58") (pinfunction "58FB7MC12_58") (pintype "bidirectional"))
      (node (ref "X2") (pin "9") (pinfunction "D7_9") (pintype "bidirectional"))
    )
    (net (code "55") (name "DB0") (class "Default")
      (node (ref "IC1") (pin "14") (pinfunction "D3_14") (pintype "bidirectional"))
      (node (ref "IC2") (pin "29") (pinfunction "D0_29") (pintype "tri_state"))
      (node (ref "IC3") (pin "93") (pinfunction "93FB4MC11_93") (pintype "bidirectional"))
    )
    (net (code "56") (name "DB1") (class "Default")
      (node (ref "IC1") (pin "13") (pinfunction "D2_13") (pintype "bidirectional"))
      (node (ref "IC2") (pin "31") (pinfunction "D1_31") (pintype "tri_state"))
      (node (ref "IC3") (pin "92") (pinfunction "92FB4MC9_92") (pintype "bidirectional"))
    )
    (net (code "57") (name "DB2") (class "Default")
      (node (ref "IC1") (pin "10") (pinfunction "D1_10") (pintype "bidirectional"))
      (node (ref "IC2") (pin "33") (pinfunction "D2_33") (pintype "tri_state"))
      (node (ref "IC3") (pin "91") (pinfunction "91FB4MC8_91") (pintype "bidirectional"))
    )
    (net (code "58") (name "DB3") (class "Default")
      (node (ref "IC1") (pin "9") (pinfunction "D0_9") (pintype "bidirectional"))
      (node (ref "IC2") (pin "35") (pinfunction "D3_35") (pintype "tri_state"))
      (node (ref "IC3") (pin "90") (pinfunction "90FB4MC6_90") (pintype "bidirectional"))
    )
    (net (code "59") (name "DB4") (class "Default")
      (node (ref "IC1") (pin "31") (pinfunction "D4_31") (pintype "bidirectional"))
      (node (ref "IC2") (pin "38") (pinfunction "D4_38") (pintype "tri_state"))
      (node (ref "IC3") (pin "89") (pinfunction "89FB4MC5_89") (pintype "bidirectional"))
    )
    (net (code "60") (name "DB5") (class "Default")
      (node (ref "IC1") (pin "32") (pinfunction "D5_32") (pintype "bidirectional"))
      (node (ref "IC2") (pin "40") (pinfunction "D5_40") (pintype "tri_state"))
      (node (ref "IC3") (pin "87") (pinfunction "87FB4MC2_87") (pintype "bidirectional"))
    )
    (net (code "61") (name "DB6") (class "Default")
      (node (ref "IC1") (pin "35") (pinfunction "D6_35") (pintype "bidirectional"))
      (node (ref "IC2") (pin "42") (pinfunction "D6_42") (pintype "tri_state"))
      (node (ref "IC3") (pin "86") (pinfunction "86FB6MC17_86") (pintype "bidirectional"))
    )
    (net (code "62") (name "DB7") (class "Default")
      (node (ref "IC1") (pin "36") (pinfunction "D7_36") (pintype "bidirectional"))
      (node (ref "IC2") (pin "44") (pinfunction "D7_44") (pintype "tri_state"))
      (node (ref "IC3") (pin "85") (pinfunction "85FB6MC15_85") (pintype "bidirectional"))
    )
    (net (code "63") (name "GND") (class "Default")
      (node (ref "C1") (pin "2") (pinfunction "2_2") (pintype "passive"))
      (node (ref "C2") (pin "2") (pinfunction "2_2") (pintype "passive"))
      (node (ref "C3") (pin "2") (pinfunction "2_2") (pintype "passive"))
      (node (ref "C4") (pin "2") (pinfunction "2_2") (pintype "passive"))
      (node (ref "C5") (pin "2") (pinfunction "2_2") (pintype "passive"))
      (node (ref "C6") (pin "2") (pinfunction "2_2") (pintype "passive"))
      (node (ref "C7") (pin "2") (pinfunction "2_2") (pintype "passive"))
      (node (ref "C8") (pin "2") (pinfunction "2_2") (pintype "passive"))
      (node (ref "GND") (pin "TP") (pinfunction "TP_TP") (pintype "input"))
      (node (ref "IC1") (pin "12") (pinfunction "GND_12") (pintype "power_in"))
      (node (ref "IC1") (pin "34") (pinfunction "GND_34") (pintype "power_in"))
      (node (ref "IC2") (pin "27") (pinfunction "GND_27") (pintype "power_in"))
      (node (ref "IC2") (pin "46") (pinfunction "GND_46") (pintype "power_in"))
      (node (ref "IC2") (pin "47") (pinfunction "~{BYTE}_47") (pintype "input"))
      (node (ref "IC3") (pin "100") (pinfunction "100GND_100") (pintype "power_in"))
      (node (ref "IC3") (pin "21") (pinfunction "21GND_21") (pintype "power_in"))
      (node (ref "IC3") (pin "31") (pinfunction "31GND_31") (pintype "power_in"))
      (node (ref "IC3") (pin "44") (pinfunction "44GND_44") (pintype "power_in"))
      (node (ref "IC3") (pin "62") (pinfunction "62GND_62") (pintype "power_in"))
      (node (ref "IC3") (pin "69") (pinfunction "69GND_69") (pintype "power_in"))
      (node (ref "IC3") (pin "75") (pinfunction "75GND_75") (pintype "power_in"))
      (node (ref "IC3") (pin "84") (pinfunction "84GND_84") (pintype "power_in"))
      (node (ref "LED1") (pin "K") (pinfunction "C_K") (pintype "passive"))
      (node (ref "LED1A") (pin "K") (pinfunction "C_K") (pintype "passive"))
      (node (ref "S1") (pin "2") (pinfunction "S_2") (pintype "passive"))
      (node (ref "S1A") (pin "2") (pinfunction "S_2") (pintype "passive"))
      (node (ref "S2") (pin "2") (pinfunction "S_2") (pintype "passive"))
      (node (ref "S2A") (pin "2") (pinfunction "S_2") (pintype "passive"))
      (node (ref "S3") (pin "1") (pinfunction "P_1") (pintype "passive"))
      (node (ref "S3A") (pin "1") (pinfunction "P_1") (pintype "passive"))
      (node (ref "VR1") (pin "1") (pinfunction "ADJ_1") (pintype "input"))
      (node (ref "WP") (pin "1") (pinfunction "1_1") (pintype "passive"))
    )
    (net (code "64") (name "LED") (class "Default")
      (node (ref "IC3") (pin "79") (pinfunction "79FB6MC9_79") (pintype "bidirectional"))
      (node (ref "R1") (pin "2") (pinfunction "2_2") (pintype "passive"))
    )
    (net (code "65") (name "Net-(IC3-45TDI)") (class "Default")
      (node (ref "IC3") (pin "45") (pinfunction "45TDI_45") (pintype "bidirectional"))
      (node (ref "TDI") (pin "TP") (pinfunction "TP_TP") (pintype "input"))
    )
    (net (code "66") (name "Net-(IC3-47TMS)") (class "Default")
      (node (ref "IC3") (pin "47") (pinfunction "47TMS_47") (pintype "bidirectional"))
      (node (ref "TMS") (pin "TP") (pinfunction "TP_TP") (pintype "input"))
    )
    (net (code "67") (name "Net-(IC3-48TCK)") (class "Default")
      (node (ref "IC3") (pin "48") (pinfunction "48TCK_48") (pintype "bidirectional"))
      (node (ref "TCK") (pin "TP") (pinfunction "TP_TP") (pintype "input"))
    )
    (net (code "68") (name "Net-(IC3-83TDO)") (class "Default")
      (node (ref "IC3") (pin "83") (pinfunction "83TDO_83") (pintype "bidirectional"))
      (node (ref "TDO") (pin "TP") (pinfunction "TP_TP") (pintype "input"))
    )
    (net (code "69") (name "Net-(LED1-PadA)") (class "Default")
      (node (ref "LED1") (pin "A") (pinfunction "A_A") (pintype "passive"))
      (node (ref "LED1A") (pin "A") (pinfunction "A_A") (pintype "passive"))
      (node (ref "R1") (pin "1") (pinfunction "1_1") (pintype "passive"))
    )
    (net (code "70") (name "SND") (class "Default")
      (node (ref "X2") (pin "Y") (pinfunction "AUDIO_Y") (pintype "passive"))
    )
    (net (code "71") (name "SW0") (class "Default")
      (node (ref "IC3") (pin "81") (pinfunction "81FB6MC12_81") (pintype "bidirectional"))
      (node (ref "R4") (pin "2") (pinfunction "2_2") (pintype "passive"))
      (node (ref "S1") (pin "1") (pinfunction "P_1") (pintype "passive"))
      (node (ref "S1A") (pin "1") (pinfunction "P_1") (pintype "passive"))
    )
    (net (code "72") (name "SW1") (class "Default")
      (node (ref "IC3") (pin "80") (pinfunction "80FB6MC11_80") (pintype "bidirectional"))
      (node (ref "R3") (pin "2") (pinfunction "2_2") (pintype "passive"))
      (node (ref "S2") (pin "1") (pinfunction "P_1") (pintype "passive"))
      (node (ref "S2A") (pin "1") (pinfunction "P_1") (pintype "passive"))
    )
    (net (code "73") (name "VR{slash}~{W}") (class "Default")
      (node (ref "IC3") (pin "36") (pinfunction "36FB5MC5_36") (pintype "bidirectional"))
      (node (ref "X2") (pin "17") (pinfunction "VR/~{W}_17") (pintype "output"))
    )
    (net (code "74") (name "unconnected-(IC2A-D8-Pad30)") (class "Default")
      (node (ref "IC2") (pin "30") (pinfunction "D8_30") (pintype "tri_state"))
    )
    (net (code "75") (name "unconnected-(IC2A-D9-Pad32)") (class "Default")
      (node (ref "IC2") (pin "32") (pinfunction "D9_32") (pintype "tri_state"))
    )
    (net (code "76") (name "unconnected-(IC2A-D10-Pad34)") (class "Default")
      (node (ref "IC2") (pin "34") (pinfunction "D10_34") (pintype "tri_state"))
    )
    (net (code "77") (name "unconnected-(IC2A-D11-Pad36)") (class "Default")
      (node (ref "IC2") (pin "36") (pinfunction "D11_36") (pintype "tri_state"))
    )
    (net (code "78") (name "unconnected-(IC2A-D12-Pad39)") (class "Default")
      (node (ref "IC2") (pin "39") (pinfunction "D12_39") (pintype "tri_state"))
    )
    (net (code "79") (name "unconnected-(IC2A-D13-Pad41)") (class "Default")
      (node (ref "IC2") (pin "41") (pinfunction "D13_41") (pintype "tri_state"))
    )
    (net (code "80") (name "unconnected-(IC2A-D14-Pad43)") (class "Default")
      (node (ref "IC2") (pin "43") (pinfunction "D14_43") (pintype "tri_state"))
    )
    (net (code "81") (name "unconnected-(IC3-27FB3MC8-I{slash}O{slash}GCK3-Pad27)") (class "Default")
      (node (ref "IC3") (pin "27") (pinfunction "27FB3MC8-I/O/GCK3_27") (pintype "bidirectional"))
    )
    (net (code "82") (name "unconnected-(IC3-28FB3MC9-Pad28)") (class "Default")
      (node (ref "IC3") (pin "28") (pinfunction "28FB3MC9_28") (pintype "bidirectional"))
    )
    (net (code "83") (name "unconnected-(IC3-29FB3MC11-Pad29)") (class "Default")
      (node (ref "IC3") (pin "29") (pinfunction "29FB3MC11_29") (pintype "bidirectional"))
    )
    (net (code "84") (name "unconnected-(IC3-76FB6MC5-Pad76)") (class "Default")
      (node (ref "IC3") (pin "76") (pinfunction "76FB6MC5_76") (pintype "bidirectional"))
    )
    (net (code "85") (name "unconnected-(IC3-77FB6MC6-Pad77)") (class "Default")
      (node (ref "IC3") (pin "77") (pinfunction "77FB6MC6_77") (pintype "bidirectional"))
    )
    (net (code "86") (name "unconnected-(IC3-78FB6MC8-Pad78)") (class "Default")
      (node (ref "IC3") (pin "78") (pinfunction "78FB6MC8_78") (pintype "bidirectional"))
    )
    (net (code "87") (name "~{BLK1}") (class "Default")
      (node (ref "IC3") (pin "55") (pinfunction "55FB7MC9_55") (pintype "bidirectional"))
      (node (ref "X2") (pin "10") (pinfunction "~{BLK1}_10") (pintype "output"))
    )
    (net (code "88") (name "~{BLK2}") (class "Default")
      (node (ref "IC3") (pin "53") (pinfunction "53FB7MC6_53") (pintype "bidirectional"))
      (node (ref "X2") (pin "11") (pinfunction "~{BLK2}_11") (pintype "output"))
    )
    (net (code "89") (name "~{BLK3}") (class "Default")
      (node (ref "IC3") (pin "49") (pinfunction "49FB5MC17_49") (pintype "bidirectional"))
      (node (ref "X2") (pin "12") (pinfunction "~{BLK3}_12") (pintype "output"))
    )
    (net (code "90") (name "~{BLK5}") (class "Default")
      (node (ref "IC3") (pin "46") (pinfunction "46FB5MC15_46") (pintype "bidirectional"))
      (node (ref "X2") (pin "13") (pinfunction "~{BLK5}_13") (pintype "output"))
    )
    (net (code "91") (name "~{FLASH_CE}") (class "Default")
      (node (ref "IC2") (pin "26") (pinfunction "~{CE}_26") (pintype "input"))
      (node (ref "IC3") (pin "95") (pinfunction "95FB4MC14_95") (pintype "bidirectional"))
    )
    (net (code "92") (name "~{IO2}") (class "Default")
      (node (ref "IC3") (pin "41") (pinfunction "41FB5MC11_41") (pintype "bidirectional"))
      (node (ref "X2") (pin "T") (pinfunction "~{IO2}_T") (pintype "output"))
    )
    (net (code "93") (name "~{IO3}") (class "Default")
      (node (ref "IC3") (pin "43") (pinfunction "43FB5MC14_43") (pintype "bidirectional"))
      (node (ref "X2") (pin "U") (pinfunction "~{IO3}_U") (pintype "output"))
    )
    (net (code "94") (name "~{IRQ}") (class "Default")
      (node (ref "IC3") (pin "32") (pinfunction "32FB3MC14_32") (pintype "bidirectional"))
      (node (ref "X2") (pin "19") (pinfunction "~{IRQ}_19") (pintype "bidirectional"))
    )
    (net (code "95") (name "~{NMI}") (class "Default")
      (node (ref "IC3") (pin "50") (pinfunction "50FB7MC2_50") (pintype "bidirectional"))
      (node (ref "X2") (pin "W") (pinfunction "~{NMI}_W") (pintype "bidirectional"))
    )
    (net (code "96") (name "~{OE}") (class "Default")
      (node (ref "IC1") (pin "41") (pinfunction "~{OE}_41") (pintype "input"))
      (node (ref "IC2") (pin "28") (pinfunction "~{OE}_28") (pintype "input"))
      (node (ref "IC3") (pin "94") (pinfunction "94FB4MC12_94") (pintype "bidirectional"))
    )
    (net (code "97") (name "~{RAM1}") (class "Default")
      (node (ref "IC3") (pin "42") (pinfunction "42FB5MC12_42") (pintype "bidirectional"))
      (node (ref "X2") (pin "14") (pinfunction "~{RAM1}_14") (pintype "output"))
    )
    (net (code "98") (name "~{RAM2}") (class "Default")
      (node (ref "IC3") (pin "40") (pinfunction "40FB5MC9_40") (pintype "bidirectional"))
      (node (ref "X2") (pin "15") (pinfunction "~{RAM2}_15") (pintype "output"))
    )
    (net (code "99") (name "~{RAM3}") (class "Default")
      (node (ref "IC3") (pin "37") (pinfunction "37FB5MC6_37") (pintype "bidirectional"))
      (node (ref "X2") (pin "16") (pinfunction "~{RAM3}_16") (pintype "output"))
    )
    (net (code "100") (name "~{RAM_CE}") (class "Default")
      (node (ref "IC1") (pin "6") (pinfunction "~{CE}_6") (pintype "input"))
      (node (ref "IC3") (pin "97") (pinfunction "97FB4MC17_97") (pintype "bidirectional"))
    )
    (net (code "101") (name "~{RB}") (class "Default")
      (node (ref "IC2") (pin "15") (pinfunction "~{RB}_15") (pintype "output"))
    )
    (net (code "102") (name "~{RESET}") (class "Default")
      (node (ref "IC2") (pin "12") (pinfunction "~{RESET}_12") (pintype "input"))
      (node (ref "IC3") (pin "99") (pinfunction "99FB2MC2-I/O/GSR_99") (pintype "bidirectional"))
      (node (ref "R2") (pin "1") (pinfunction "1_1") (pintype "passive"))
      (node (ref "S3") (pin "2") (pinfunction "S_2") (pintype "passive"))
      (node (ref "S3A") (pin "2") (pinfunction "S_2") (pintype "passive"))
      (node (ref "X2") (pin "X") (pinfunction "~{RESET}_X") (pintype "bidirectional"))
    )
    (net (code "103") (name "~{WE}") (class "Default")
      (node (ref "IC1") (pin "17") (pinfunction "~{WE}_17") (pintype "input"))
      (node (ref "IC2") (pin "11") (pinfunction "~{WE}_11") (pintype "input"))
      (node (ref "IC3") (pin "13") (pinfunction "13FB1MC5_13") (pintype "bidirectional"))
    )
  )
)
